# Midio.net
KiCad netlist of a schematic drawn in EAGLE
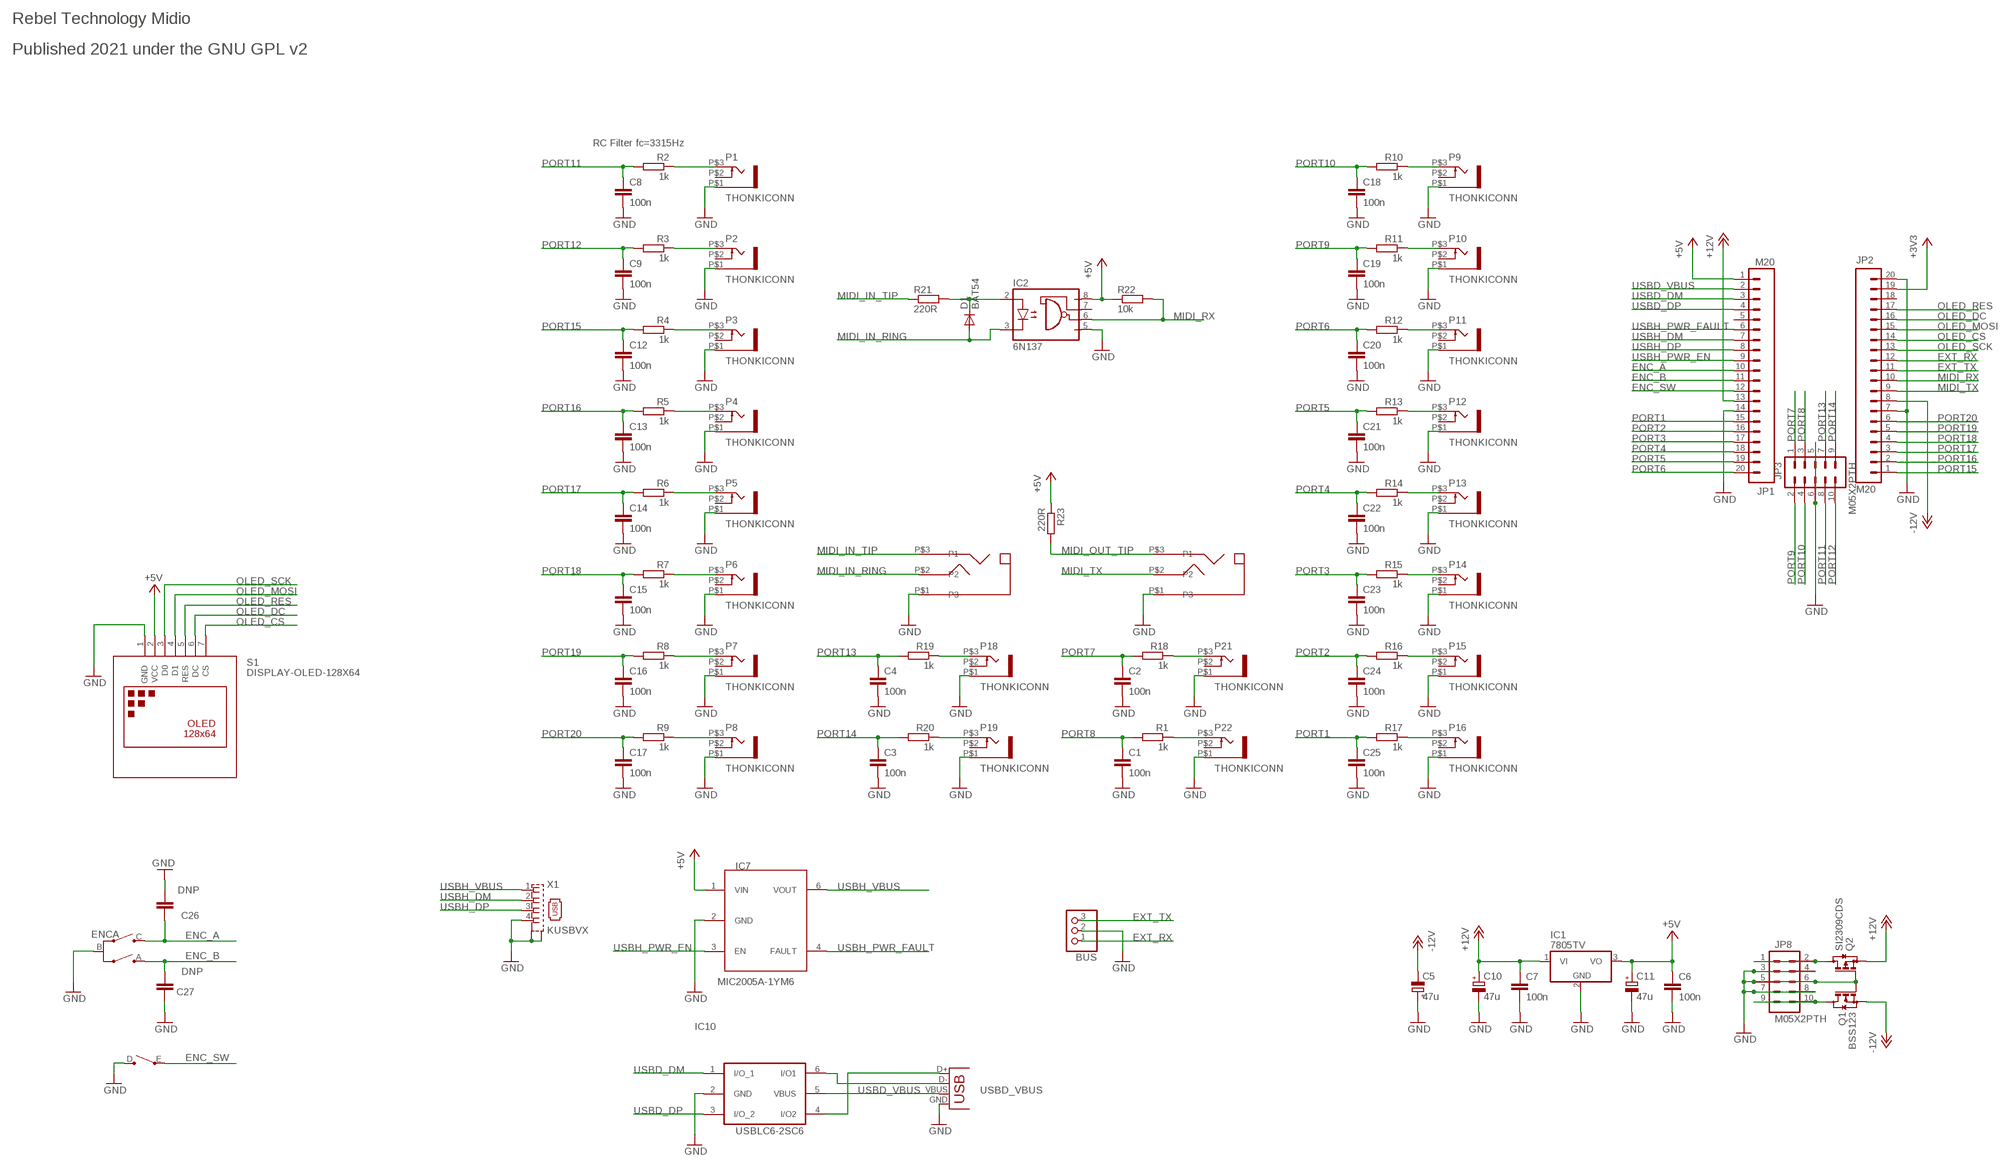
[diagram p0: schematic, sheet 1]

(export (version "E")
  (design (tool "Eeschema 10.0.6"))
  (components
    (comp (ref "BUS")
      (value "CON-JST-1X03PH-TH")
      (footprint "eagle-import:JST-B3B-PH-KL")
      (libsource (lib "eagle-import") (part "CON-JST-1X03PH-TH"))
    )
    (comp (ref "C1")
      (value "100n")
      (footprint "eagle-import:C0603")
      (libsource (lib "eagle-import") (part "C-EUC0603"))
    )
    (comp (ref "C2")
      (value "100n")
      (footprint "eagle-import:C0603")
      (libsource (lib "eagle-import") (part "C-EUC0603"))
    )
    (comp (ref "C3")
      (value "100n")
      (footprint "eagle-import:C0603")
      (libsource (lib "eagle-import") (part "C-EUC0603"))
    )
    (comp (ref "C4")
      (value "100n")
      (footprint "eagle-import:C0603")
      (libsource (lib "eagle-import") (part "C-EUC0603"))
    )
    (comp (ref "C5")
      (value "47u")
      (footprint "eagle-import:UD-4X5,8_NICHICON")
      (libsource (lib "eagle-import") (part "CPOL-EUUD-4X5,8"))
    )
    (comp (ref "C6")
      (value "100n")
      (footprint "eagle-import:C0603")
      (libsource (lib "eagle-import") (part "C-EUC0603"))
    )
    (comp (ref "C7")
      (value "100n")
      (footprint "eagle-import:C0603")
      (libsource (lib "eagle-import") (part "C-EUC0603"))
    )
    (comp (ref "C8")
      (value "100n")
      (footprint "eagle-import:C0603")
      (libsource (lib "eagle-import") (part "C-EUC0603"))
    )
    (comp (ref "C9")
      (value "100n")
      (footprint "eagle-import:C0603")
      (libsource (lib "eagle-import") (part "C-EUC0603"))
    )
    (comp (ref "C10")
      (value "47u")
      (footprint "eagle-import:UD-4X5,8_NICHICON")
      (libsource (lib "eagle-import") (part "CPOL-EUUD-4X5,8"))
    )
    (comp (ref "C11")
      (value "47u")
      (footprint "eagle-import:UD-4X5,8_NICHICON")
      (libsource (lib "eagle-import") (part "rcl_CPOL-EUUD-4X5,8"))
    )
    (comp (ref "C12")
      (value "100n")
      (footprint "eagle-import:C0603")
      (libsource (lib "eagle-import") (part "C-EUC0603"))
    )
    (comp (ref "C13")
      (value "100n")
      (footprint "eagle-import:C0603")
      (libsource (lib "eagle-import") (part "C-EUC0603"))
    )
    (comp (ref "C14")
      (value "100n")
      (footprint "eagle-import:C0603")
      (libsource (lib "eagle-import") (part "C-EUC0603"))
    )
    (comp (ref "C15")
      (value "100n")
      (footprint "eagle-import:C0603")
      (libsource (lib "eagle-import") (part "C-EUC0603"))
    )
    (comp (ref "C16")
      (value "100n")
      (footprint "eagle-import:C0603")
      (libsource (lib "eagle-import") (part "C-EUC0603"))
    )
    (comp (ref "C17")
      (value "100n")
      (footprint "eagle-import:C0603")
      (libsource (lib "eagle-import") (part "C-EUC0603"))
    )
    (comp (ref "C18")
      (value "100n")
      (footprint "eagle-import:C0603")
      (libsource (lib "eagle-import") (part "C-EUC0603"))
    )
    (comp (ref "C19")
      (value "100n")
      (footprint "eagle-import:C0603")
      (libsource (lib "eagle-import") (part "C-EUC0603"))
    )
    (comp (ref "C20")
      (value "100n")
      (footprint "eagle-import:C0603")
      (libsource (lib "eagle-import") (part "C-EUC0603"))
    )
    (comp (ref "C21")
      (value "100n")
      (footprint "eagle-import:C0603")
      (libsource (lib "eagle-import") (part "C-EUC0603"))
    )
    (comp (ref "C22")
      (value "100n")
      (footprint "eagle-import:C0603")
      (libsource (lib "eagle-import") (part "C-EUC0603"))
    )
    (comp (ref "C23")
      (value "100n")
      (footprint "eagle-import:C0603")
      (libsource (lib "eagle-import") (part "C-EUC0603"))
    )
    (comp (ref "C24")
      (value "100n")
      (footprint "eagle-import:C0603")
      (libsource (lib "eagle-import") (part "C-EUC0603"))
    )
    (comp (ref "C25")
      (value "100n")
      (footprint "eagle-import:C0603")
      (libsource (lib "eagle-import") (part "C-EUC0603"))
    )
    (comp (ref "C26")
      (value "DNP")
      (footprint "eagle-import:C0603")
      (libsource (lib "eagle-import") (part "rcl_C-EUC0603"))
    )
    (comp (ref "C27")
      (value "DNP")
      (footprint "eagle-import:C0603")
      (libsource (lib "eagle-import") (part "rcl_C-EUC0603"))
    )
    (comp (ref "D1")
      (value "BAT54")
      (footprint "eagle-import:SOT23-R")
      (libsource (lib "eagle-import") (part "DIODESOT23_REFLOW"))
    )
    (comp (ref "ENC")
      (value "CI-11")
      (footprint "eagle-import:CI-11")
      (libsource (lib "eagle-import") (part "CI-11"))
    )
    (comp (ref "IC1")
      (value "7805TV")
      (footprint "eagle-import:TO220V")
      (libsource (lib "eagle-import") (part "78TV05"))
    )
    (comp (ref "IC2")
      (value "6N137")
      (footprint "eagle-import:DIL08")
      (libsource (lib "eagle-import") (part "6N137"))
    )
    (comp (ref "IC7")
      (value "MIC2005A-1YM6")
      (footprint "eagle-import:SOT23-6")
      (libsource (lib "eagle-import") (part "MIC2005"))
    )
    (comp (ref "IC10")
      (value "USBLC6-2SC6")
      (footprint "eagle-import:SOT-23-6L")
      (libsource (lib "eagle-import") (part "USBLC6-2SC6"))
    )
    (comp (ref "J1")
      (value "THONKICONN_STEREO")
      (footprint "eagle-import:THONKICONN_STEREO")
      (libsource (lib "eagle-import") (part "THONKICONN_STEREO"))
    )
    (comp (ref "J2")
      (value "THONKICONN_STEREO")
      (footprint "eagle-import:THONKICONN_STEREO")
      (libsource (lib "eagle-import") (part "THONKICONN_STEREO"))
    )
    (comp (ref "JP1")
      (value "M20")
      (footprint "eagle-import:1X20")
      (libsource (lib "eagle-import") (part "M20"))
    )
    (comp (ref "JP2")
      (value "M20")
      (footprint "eagle-import:1X20")
      (libsource (lib "eagle-import") (part "M20"))
    )
    (comp (ref "JP3")
      (value "M05X2PTH")
      (footprint "eagle-import:AVR_ICSP")
      (libsource (lib "eagle-import") (part "M05X2PTH"))
    )
    (comp (ref "JP8")
      (value "M05X2PTH")
      (footprint "eagle-import:AVR_ICSP")
      (libsource (lib "eagle-import") (part "M05X2PTH"))
    )
    (comp (ref "P1")
      (value "THONKICONN")
      (footprint "eagle-import:THONKICONN")
      (libsource (lib "eagle-import") (part "THONKICONN"))
    )
    (comp (ref "P2")
      (value "THONKICONN")
      (footprint "eagle-import:THONKICONN")
      (libsource (lib "eagle-import") (part "THONKICONN"))
    )
    (comp (ref "P3")
      (value "THONKICONN")
      (footprint "eagle-import:THONKICONN")
      (libsource (lib "eagle-import") (part "THONKICONN"))
    )
    (comp (ref "P4")
      (value "THONKICONN")
      (footprint "eagle-import:THONKICONN")
      (libsource (lib "eagle-import") (part "THONKICONN"))
    )
    (comp (ref "P5")
      (value "THONKICONN")
      (footprint "eagle-import:THONKICONN")
      (libsource (lib "eagle-import") (part "THONKICONN"))
    )
    (comp (ref "P6")
      (value "THONKICONN")
      (footprint "eagle-import:THONKICONN")
      (libsource (lib "eagle-import") (part "THONKICONN"))
    )
    (comp (ref "P7")
      (value "THONKICONN")
      (footprint "eagle-import:THONKICONN")
      (libsource (lib "eagle-import") (part "THONKICONN"))
    )
    (comp (ref "P8")
      (value "THONKICONN")
      (footprint "eagle-import:THONKICONN")
      (libsource (lib "eagle-import") (part "THONKICONN"))
    )
    (comp (ref "P9")
      (value "THONKICONN")
      (footprint "eagle-import:THONKICONN")
      (libsource (lib "eagle-import") (part "THONKICONN"))
    )
    (comp (ref "P10")
      (value "THONKICONN")
      (footprint "eagle-import:THONKICONN")
      (libsource (lib "eagle-import") (part "THONKICONN"))
    )
    (comp (ref "P11")
      (value "THONKICONN")
      (footprint "eagle-import:THONKICONN")
      (libsource (lib "eagle-import") (part "THONKICONN"))
    )
    (comp (ref "P12")
      (value "THONKICONN")
      (footprint "eagle-import:THONKICONN")
      (libsource (lib "eagle-import") (part "THONKICONN"))
    )
    (comp (ref "P13")
      (value "THONKICONN")
      (footprint "eagle-import:THONKICONN")
      (libsource (lib "eagle-import") (part "THONKICONN"))
    )
    (comp (ref "P14")
      (value "THONKICONN")
      (footprint "eagle-import:THONKICONN")
      (libsource (lib "eagle-import") (part "THONKICONN"))
    )
    (comp (ref "P15")
      (value "THONKICONN")
      (footprint "eagle-import:THONKICONN")
      (libsource (lib "eagle-import") (part "THONKICONN"))
    )
    (comp (ref "P16")
      (value "THONKICONN")
      (footprint "eagle-import:THONKICONN")
      (libsource (lib "eagle-import") (part "THONKICONN"))
    )
    (comp (ref "P18")
      (value "THONKICONN")
      (footprint "eagle-import:THONKICONN")
      (libsource (lib "eagle-import") (part "THONKICONN"))
    )
    (comp (ref "P19")
      (value "THONKICONN")
      (footprint "eagle-import:THONKICONN")
      (libsource (lib "eagle-import") (part "THONKICONN"))
    )
    (comp (ref "P21")
      (value "THONKICONN")
      (footprint "eagle-import:THONKICONN")
      (libsource (lib "eagle-import") (part "THONKICONN"))
    )
    (comp (ref "P22")
      (value "THONKICONN")
      (footprint "eagle-import:THONKICONN")
      (libsource (lib "eagle-import") (part "THONKICONN"))
    )
    (comp (ref "Q1")
      (value "BSS123")
      (footprint "eagle-import:SOT23")
      (libsource (lib "eagle-import") (part "BSS123"))
    )
    (comp (ref "Q2")
      (value "SI2309CDS")
      (footprint "eagle-import:SOT23")
      (libsource (lib "eagle-import") (part "BSS84"))
    )
    (comp (ref "R1")
      (value "1k")
      (footprint "eagle-import:0603")
      (libsource (lib "eagle-import") (part "R-EU_0603"))
    )
    (comp (ref "R2")
      (value "1k")
      (footprint "eagle-import:0603")
      (libsource (lib "eagle-import") (part "R-EU_0603"))
    )
    (comp (ref "R3")
      (value "1k")
      (footprint "eagle-import:0603")
      (libsource (lib "eagle-import") (part "R-EU_0603"))
    )
    (comp (ref "R4")
      (value "1k")
      (footprint "eagle-import:0603")
      (libsource (lib "eagle-import") (part "R-EU_0603"))
    )
    (comp (ref "R5")
      (value "1k")
      (footprint "eagle-import:0603")
      (libsource (lib "eagle-import") (part "R-EU_0603"))
    )
    (comp (ref "R6")
      (value "1k")
      (footprint "eagle-import:0603")
      (libsource (lib "eagle-import") (part "R-EU_0603"))
    )
    (comp (ref "R7")
      (value "1k")
      (footprint "eagle-import:0603")
      (libsource (lib "eagle-import") (part "R-EU_0603"))
    )
    (comp (ref "R8")
      (value "1k")
      (footprint "eagle-import:0603")
      (libsource (lib "eagle-import") (part "R-EU_0603"))
    )
    (comp (ref "R9")
      (value "1k")
      (footprint "eagle-import:0603")
      (libsource (lib "eagle-import") (part "R-EU_0603"))
    )
    (comp (ref "R10")
      (value "1k")
      (footprint "eagle-import:0603")
      (libsource (lib "eagle-import") (part "R-EU_0603"))
    )
    (comp (ref "R11")
      (value "1k")
      (footprint "eagle-import:0603")
      (libsource (lib "eagle-import") (part "R-EU_0603"))
    )
    (comp (ref "R12")
      (value "1k")
      (footprint "eagle-import:0603")
      (libsource (lib "eagle-import") (part "R-EU_0603"))
    )
    (comp (ref "R13")
      (value "1k")
      (footprint "eagle-import:0603")
      (libsource (lib "eagle-import") (part "R-EU_0603"))
    )
    (comp (ref "R14")
      (value "1k")
      (footprint "eagle-import:0603")
      (libsource (lib "eagle-import") (part "R-EU_0603"))
    )
    (comp (ref "R15")
      (value "1k")
      (footprint "eagle-import:0603")
      (libsource (lib "eagle-import") (part "R-EU_0603"))
    )
    (comp (ref "R16")
      (value "1k")
      (footprint "eagle-import:0603")
      (libsource (lib "eagle-import") (part "R-EU_0603"))
    )
    (comp (ref "R17")
      (value "1k")
      (footprint "eagle-import:0603")
      (libsource (lib "eagle-import") (part "R-EU_0603"))
    )
    (comp (ref "R18")
      (value "1k")
      (footprint "eagle-import:0603")
      (libsource (lib "eagle-import") (part "R-EU_0603"))
    )
    (comp (ref "R19")
      (value "1k")
      (footprint "eagle-import:0603")
      (libsource (lib "eagle-import") (part "R-EU_0603"))
    )
    (comp (ref "R20")
      (value "1k")
      (footprint "eagle-import:0603")
      (libsource (lib "eagle-import") (part "R-EU_0603"))
    )
    (comp (ref "R21")
      (value "220R")
      (footprint "eagle-import:0603")
      (libsource (lib "eagle-import") (part "Rebel_15457297_R-EU_0603"))
    )
    (comp (ref "R22")
      (value "10k")
      (footprint "eagle-import:0603")
      (libsource (lib "eagle-import") (part "Rebel_15457297_R-EU_0603"))
    )
    (comp (ref "R23")
      (value "220R")
      (footprint "eagle-import:0603")
      (libsource (lib "eagle-import") (part "Rebel_15457297_R-EU_0603"))
    )
    (comp (ref "S1")
      (value "DISPLAY-OLED-128X64")
      (footprint "eagle-import:DISPLAY-OLED-128X64")
      (libsource (lib "eagle-import") (part "DISPLAY-OLED-128X64"))
    )
    (comp (ref "X1")
      (value "KUSBVX")
      (footprint "eagle-import:KUSBVX")
      (libsource (lib "eagle-import") (part "KUSBVX"))
    )
    (comp (ref "X2")
      (value "USBPTH-VERTICAL")
      (footprint "eagle-import:USB-B-PTH-VERTICAL")
      (libsource (lib "eagle-import") (part "USBPTH-VERTICAL"))
    )
  )
  (nets
    (net (code "1") (name "+3V3") (class "Default")
      (node (ref "JP2") (pin "19") (pinfunction "19_19") (pintype "passive"))
    )
    (net (code "2") (name "+5V") (class "Default")
      (node (ref "C11") (pin "+") (pinfunction "+_+") (pintype "passive"))
      (node (ref "C6") (pin "1") (pinfunction "1_1") (pintype "passive"))
      (node (ref "IC1") (pin "3") (pinfunction "VO_3") (pintype "passive"))
      (node (ref "IC2") (pin "8") (pinfunction "VCC_8") (pintype "passive"))
      (node (ref "IC7") (pin "1") (pinfunction "VIN_1") (pintype "power_in"))
      (node (ref "JP1") (pin "1") (pinfunction "1_1") (pintype "passive"))
      (node (ref "R22") (pin "1") (pinfunction "1_1") (pintype "passive"))
      (node (ref "R23") (pin "1") (pinfunction "1_1") (pintype "passive"))
      (node (ref "S1") (pin "2") (pinfunction "VCC_2") (pintype "power_in"))
    )
    (net (code "3") (name "+12V") (class "Default")
      (node (ref "C10") (pin "+") (pinfunction "+_+") (pintype "passive"))
      (node (ref "C7") (pin "1") (pinfunction "1_1") (pintype "passive"))
      (node (ref "IC1") (pin "1") (pinfunction "VI_1") (pintype "input"))
      (node (ref "JP1") (pin "13") (pinfunction "13_13") (pintype "passive"))
      (node (ref "Q2") (pin "2") (pinfunction "S_2") (pintype "passive"))
    )
    (net (code "4") (name "-12V") (class "Default")
      (node (ref "C5") (pin "-") (pinfunction "-_-") (pintype "passive"))
      (node (ref "JP2") (pin "8") (pinfunction "8_8") (pintype "passive"))
      (node (ref "Q1") (pin "2") (pinfunction "S_2") (pintype "passive"))
    )
    (net (code "5") (name "/ENC_A") (class "Default")
      (node (ref "C26") (pin "1") (pinfunction "1_1") (pintype "passive"))
      (node (ref "ENC") (pin "C") (pinfunction "B_C") (pintype "passive"))
      (node (ref "JP1") (pin "10") (pinfunction "10_10") (pintype "passive"))
    )
    (net (code "6") (name "/ENC_B") (class "Default")
      (node (ref "C27") (pin "1") (pinfunction "1_1") (pintype "passive"))
      (node (ref "ENC") (pin "A") (pinfunction "A_A") (pintype "passive"))
      (node (ref "JP1") (pin "11") (pinfunction "11_11") (pintype "passive"))
    )
    (net (code "7") (name "/ENC_SW") (class "Default")
      (node (ref "ENC") (pin "E") (pinfunction "E_E") (pintype "passive"))
      (node (ref "JP1") (pin "12") (pinfunction "12_12") (pintype "passive"))
    )
    (net (code "8") (name "/EXT_RX") (class "Default")
      (node (ref "BUS") (pin "1") (pinfunction "1_1") (pintype "passive"))
      (node (ref "JP2") (pin "12") (pinfunction "12_12") (pintype "passive"))
    )
    (net (code "9") (name "/EXT_TX") (class "Default")
      (node (ref "BUS") (pin "3") (pinfunction "3_3") (pintype "passive"))
      (node (ref "JP2") (pin "11") (pinfunction "11_11") (pintype "passive"))
    )
    (net (code "10") (name "/MIDI_IN_RING") (class "Default")
      (node (ref "D1") (pin "1") (pinfunction "A_1") (pintype "passive"))
      (node (ref "IC2") (pin "3") (pinfunction "C_3") (pintype "passive"))
      (node (ref "J1") (pin "P$2") (pinfunction "P2_P$2") (pintype "bidirectional"))
    )
    (net (code "11") (name "/MIDI_IN_TIP") (class "Default")
      (node (ref "J1") (pin "P$3") (pinfunction "P1_P$3") (pintype "bidirectional"))
      (node (ref "R21") (pin "1") (pinfunction "1_1") (pintype "passive"))
    )
    (net (code "12") (name "/MIDI_OUT_TIP") (class "Default")
      (node (ref "J2") (pin "P$3") (pinfunction "P1_P$3") (pintype "bidirectional"))
      (node (ref "R23") (pin "2") (pinfunction "2_2") (pintype "passive"))
    )
    (net (code "13") (name "/MIDI_RX") (class "Default")
      (node (ref "IC2") (pin "6") (pinfunction "VO_6") (pintype "passive"))
      (node (ref "JP2") (pin "10") (pinfunction "10_10") (pintype "passive"))
      (node (ref "R22") (pin "2") (pinfunction "2_2") (pintype "passive"))
    )
    (net (code "14") (name "/MIDI_TX") (class "Default")
      (node (ref "J2") (pin "P$2") (pinfunction "P2_P$2") (pintype "bidirectional"))
      (node (ref "JP2") (pin "9") (pinfunction "9_9") (pintype "passive"))
    )
    (net (code "15") (name "/OLED_CS") (class "Default")
      (node (ref "JP2") (pin "14") (pinfunction "14_14") (pintype "passive"))
      (node (ref "S1") (pin "7") (pinfunction "CS_7") (pintype "bidirectional"))
    )
    (net (code "16") (name "/OLED_DC") (class "Default")
      (node (ref "JP2") (pin "16") (pinfunction "16_16") (pintype "passive"))
      (node (ref "S1") (pin "6") (pinfunction "DC_6") (pintype "bidirectional"))
    )
    (net (code "17") (name "/OLED_MOSI") (class "Default")
      (node (ref "JP2") (pin "15") (pinfunction "15_15") (pintype "passive"))
      (node (ref "S1") (pin "4") (pinfunction "D1_4") (pintype "bidirectional"))
    )
    (net (code "18") (name "/OLED_RES") (class "Default")
      (node (ref "JP2") (pin "17") (pinfunction "17_17") (pintype "passive"))
      (node (ref "S1") (pin "5") (pinfunction "RES_5") (pintype "bidirectional"))
    )
    (net (code "19") (name "/OLED_SCK") (class "Default")
      (node (ref "JP2") (pin "13") (pinfunction "13_13") (pintype "passive"))
      (node (ref "S1") (pin "3") (pinfunction "D0_3") (pintype "bidirectional"))
    )
    (net (code "20") (name "/PORT1") (class "Default")
      (node (ref "C25") (pin "1") (pinfunction "1_1") (pintype "passive"))
      (node (ref "JP1") (pin "15") (pinfunction "15_15") (pintype "passive"))
      (node (ref "R17") (pin "2") (pinfunction "2_2") (pintype "passive"))
    )
    (net (code "21") (name "/PORT2") (class "Default")
      (node (ref "C24") (pin "1") (pinfunction "1_1") (pintype "passive"))
      (node (ref "JP1") (pin "16") (pinfunction "16_16") (pintype "passive"))
      (node (ref "R16") (pin "2") (pinfunction "2_2") (pintype "passive"))
    )
    (net (code "22") (name "/PORT3") (class "Default")
      (node (ref "C23") (pin "1") (pinfunction "1_1") (pintype "passive"))
      (node (ref "JP1") (pin "17") (pinfunction "17_17") (pintype "passive"))
      (node (ref "R15") (pin "2") (pinfunction "2_2") (pintype "passive"))
    )
    (net (code "23") (name "/PORT4") (class "Default")
      (node (ref "C22") (pin "1") (pinfunction "1_1") (pintype "passive"))
      (node (ref "JP1") (pin "18") (pinfunction "18_18") (pintype "passive"))
      (node (ref "R14") (pin "2") (pinfunction "2_2") (pintype "passive"))
    )
    (net (code "24") (name "/PORT5") (class "Default")
      (node (ref "C21") (pin "1") (pinfunction "1_1") (pintype "passive"))
      (node (ref "JP1") (pin "19") (pinfunction "19_19") (pintype "passive"))
      (node (ref "R13") (pin "2") (pinfunction "2_2") (pintype "passive"))
    )
    (net (code "25") (name "/PORT6") (class "Default")
      (node (ref "C20") (pin "1") (pinfunction "1_1") (pintype "passive"))
      (node (ref "JP1") (pin "20") (pinfunction "20_20") (pintype "passive"))
      (node (ref "R12") (pin "2") (pinfunction "2_2") (pintype "passive"))
    )
    (net (code "26") (name "/PORT7") (class "Default")
      (node (ref "C2") (pin "1") (pinfunction "1_1") (pintype "passive"))
      (node (ref "JP3") (pin "1") (pinfunction "1_1") (pintype "passive"))
      (node (ref "R18") (pin "2") (pinfunction "2_2") (pintype "passive"))
    )
    (net (code "27") (name "/PORT8") (class "Default")
      (node (ref "C1") (pin "1") (pinfunction "1_1") (pintype "passive"))
      (node (ref "JP3") (pin "3") (pinfunction "3_3") (pintype "passive"))
      (node (ref "R1") (pin "2") (pinfunction "2_2") (pintype "passive"))
    )
    (net (code "28") (name "/PORT9") (class "Default")
      (node (ref "C19") (pin "1") (pinfunction "1_1") (pintype "passive"))
      (node (ref "JP3") (pin "2") (pinfunction "2_2") (pintype "passive"))
      (node (ref "R11") (pin "2") (pinfunction "2_2") (pintype "passive"))
    )
    (net (code "29") (name "/PORT10") (class "Default")
      (node (ref "C18") (pin "1") (pinfunction "1_1") (pintype "passive"))
      (node (ref "JP3") (pin "4") (pinfunction "4_4") (pintype "passive"))
      (node (ref "R10") (pin "2") (pinfunction "2_2") (pintype "passive"))
    )
    (net (code "30") (name "/PORT11") (class "Default")
      (node (ref "C8") (pin "1") (pinfunction "1_1") (pintype "passive"))
      (node (ref "JP3") (pin "8") (pinfunction "8_8") (pintype "passive"))
      (node (ref "R2") (pin "2") (pinfunction "2_2") (pintype "passive"))
    )
    (net (code "31") (name "/PORT12") (class "Default")
      (node (ref "C9") (pin "1") (pinfunction "1_1") (pintype "passive"))
      (node (ref "JP3") (pin "10") (pinfunction "10_10") (pintype "passive"))
      (node (ref "R3") (pin "2") (pinfunction "2_2") (pintype "passive"))
    )
    (net (code "32") (name "/PORT13") (class "Default")
      (node (ref "C4") (pin "1") (pinfunction "1_1") (pintype "passive"))
      (node (ref "JP3") (pin "7") (pinfunction "7_7") (pintype "passive"))
      (node (ref "R19") (pin "2") (pinfunction "2_2") (pintype "passive"))
    )
    (net (code "33") (name "/PORT14") (class "Default")
      (node (ref "C3") (pin "1") (pinfunction "1_1") (pintype "passive"))
      (node (ref "JP3") (pin "9") (pinfunction "9_9") (pintype "passive"))
      (node (ref "R20") (pin "2") (pinfunction "2_2") (pintype "passive"))
    )
    (net (code "34") (name "/PORT15") (class "Default")
      (node (ref "C12") (pin "1") (pinfunction "1_1") (pintype "passive"))
      (node (ref "JP2") (pin "1") (pinfunction "1_1") (pintype "passive"))
      (node (ref "R4") (pin "2") (pinfunction "2_2") (pintype "passive"))
    )
    (net (code "35") (name "/PORT16") (class "Default")
      (node (ref "C13") (pin "1") (pinfunction "1_1") (pintype "passive"))
      (node (ref "JP2") (pin "2") (pinfunction "2_2") (pintype "passive"))
      (node (ref "R5") (pin "2") (pinfunction "2_2") (pintype "passive"))
    )
    (net (code "36") (name "/PORT17") (class "Default")
      (node (ref "C14") (pin "1") (pinfunction "1_1") (pintype "passive"))
      (node (ref "JP2") (pin "3") (pinfunction "3_3") (pintype "passive"))
      (node (ref "R6") (pin "2") (pinfunction "2_2") (pintype "passive"))
    )
    (net (code "37") (name "/PORT18") (class "Default")
      (node (ref "C15") (pin "1") (pinfunction "1_1") (pintype "passive"))
      (node (ref "JP2") (pin "4") (pinfunction "4_4") (pintype "passive"))
      (node (ref "R7") (pin "2") (pinfunction "2_2") (pintype "passive"))
    )
    (net (code "38") (name "/PORT19") (class "Default")
      (node (ref "C16") (pin "1") (pinfunction "1_1") (pintype "passive"))
      (node (ref "JP2") (pin "5") (pinfunction "5_5") (pintype "passive"))
      (node (ref "R8") (pin "2") (pinfunction "2_2") (pintype "passive"))
    )
    (net (code "39") (name "/PORT20") (class "Default")
      (node (ref "C17") (pin "1") (pinfunction "1_1") (pintype "passive"))
      (node (ref "JP2") (pin "6") (pinfunction "6_6") (pintype "passive"))
      (node (ref "R9") (pin "2") (pinfunction "2_2") (pintype "passive"))
    )
    (net (code "40") (name "/USBD_DM") (class "Default")
      (node (ref "IC10") (pin "1") (pinfunction "I/O_1_1") (pintype "bidirectional"))
      (node (ref "JP1") (pin "3") (pinfunction "3_3") (pintype "passive"))
    )
    (net (code "41") (name "/USBD_DP") (class "Default")
      (node (ref "IC10") (pin "3") (pinfunction "I/O_2_3") (pintype "bidirectional"))
      (node (ref "JP1") (pin "4") (pinfunction "4_4") (pintype "passive"))
    )
    (net (code "42") (name "/USBD_VBUS") (class "Default")
      (node (ref "IC10") (pin "5") (pinfunction "VBUS_5") (pintype "bidirectional"))
      (node (ref "JP1") (pin "2") (pinfunction "2_2") (pintype "passive"))
      (node (ref "X2") (pin "VBUS") (pinfunction "VBUS_VBUS") (pintype "bidirectional"))
    )
    (net (code "43") (name "/USBH_DM") (class "Default")
      (node (ref "JP1") (pin "7") (pinfunction "7_7") (pintype "passive"))
      (node (ref "X1") (pin "2") (pinfunction "2_2") (pintype "passive"))
    )
    (net (code "44") (name "/USBH_DP") (class "Default")
      (node (ref "JP1") (pin "8") (pinfunction "8_8") (pintype "passive"))
      (node (ref "X1") (pin "3") (pinfunction "3_3") (pintype "passive"))
    )
    (net (code "45") (name "/USBH_PWR_EN") (class "Default")
      (node (ref "IC7") (pin "3") (pinfunction "EN_3") (pintype "input"))
      (node (ref "JP1") (pin "9") (pinfunction "9_9") (pintype "passive"))
    )
    (net (code "46") (name "/USBH_PWR_FAULT") (class "Default")
      (node (ref "IC7") (pin "4") (pinfunction "FAULT_4") (pintype "output"))
      (node (ref "JP1") (pin "6") (pinfunction "6_6") (pintype "passive"))
    )
    (net (code "47") (name "/USBH_VBUS") (class "Default")
      (node (ref "IC7") (pin "6") (pinfunction "VOUT_6") (pintype "output"))
      (node (ref "X1") (pin "1") (pinfunction "1_1") (pintype "passive"))
    )
    (net (code "48") (name "GND") (class "Default")
      (node (ref "BUS") (pin "2") (pinfunction "2_2") (pintype "passive"))
      (node (ref "C1") (pin "2") (pinfunction "2_2") (pintype "passive"))
      (node (ref "C10") (pin "-") (pinfunction "-_-") (pintype "passive"))
      (node (ref "C11") (pin "-") (pinfunction "-_-") (pintype "passive"))
      (node (ref "C12") (pin "2") (pinfunction "2_2") (pintype "passive"))
      (node (ref "C13") (pin "2") (pinfunction "2_2") (pintype "passive"))
      (node (ref "C14") (pin "2") (pinfunction "2_2") (pintype "passive"))
      (node (ref "C15") (pin "2") (pinfunction "2_2") (pintype "passive"))
      (node (ref "C16") (pin "2") (pinfunction "2_2") (pintype "passive"))
      (node (ref "C17") (pin "2") (pinfunction "2_2") (pintype "passive"))
      (node (ref "C18") (pin "2") (pinfunction "2_2") (pintype "passive"))
      (node (ref "C19") (pin "2") (pinfunction "2_2") (pintype "passive"))
      (node (ref "C2") (pin "2") (pinfunction "2_2") (pintype "passive"))
      (node (ref "C20") (pin "2") (pinfunction "2_2") (pintype "passive"))
      (node (ref "C21") (pin "2") (pinfunction "2_2") (pintype "passive"))
      (node (ref "C22") (pin "2") (pinfunction "2_2") (pintype "passive"))
      (node (ref "C23") (pin "2") (pinfunction "2_2") (pintype "passive"))
      (node (ref "C24") (pin "2") (pinfunction "2_2") (pintype "passive"))
      (node (ref "C25") (pin "2") (pinfunction "2_2") (pintype "passive"))
      (node (ref "C26") (pin "2") (pinfunction "2_2") (pintype "passive"))
      (node (ref "C27") (pin "2") (pinfunction "2_2") (pintype "passive"))
      (node (ref "C3") (pin "2") (pinfunction "2_2") (pintype "passive"))
      (node (ref "C4") (pin "2") (pinfunction "2_2") (pintype "passive"))
      (node (ref "C5") (pin "+") (pinfunction "+_+") (pintype "passive"))
      (node (ref "C6") (pin "2") (pinfunction "2_2") (pintype "passive"))
      (node (ref "C7") (pin "2") (pinfunction "2_2") (pintype "passive"))
      (node (ref "C8") (pin "2") (pinfunction "2_2") (pintype "passive"))
      (node (ref "C9") (pin "2") (pinfunction "2_2") (pintype "passive"))
      (node (ref "ENC") (pin "B") (pinfunction "C_B") (pintype "passive"))
      (node (ref "ENC") (pin "D") (pinfunction "D_D") (pintype "passive"))
      (node (ref "IC1") (pin "2") (pinfunction "GND_2") (pintype "passive"))
      (node (ref "IC10") (pin "2") (pinfunction "GND_2") (pintype "bidirectional"))
      (node (ref "IC2") (pin "5") (pinfunction "GND_5") (pintype "passive"))
      (node (ref "IC7") (pin "2") (pinfunction "GND_2") (pintype "power_in"))
      (node (ref "J1") (pin "P$1") (pinfunction "P3_P$1") (pintype "bidirectional"))
      (node (ref "J2") (pin "P$1") (pinfunction "P3_P$1") (pintype "bidirectional"))
      (node (ref "JP1") (pin "14") (pinfunction "14_14") (pintype "passive"))
      (node (ref "JP2") (pin "20") (pinfunction "20_20") (pintype "passive"))
      (node (ref "JP2") (pin "7") (pinfunction "7_7") (pintype "passive"))
      (node (ref "JP3") (pin "5") (pinfunction "5_5") (pintype "passive"))
      (node (ref "JP3") (pin "6") (pinfunction "6_6") (pintype "passive"))
      (node (ref "JP8") (pin "3") (pinfunction "3_3") (pintype "passive"))
      (node (ref "JP8") (pin "4") (pinfunction "4_4") (pintype "passive"))
      (node (ref "JP8") (pin "5") (pinfunction "5_5") (pintype "passive"))
      (node (ref "JP8") (pin "6") (pinfunction "6_6") (pintype "passive"))
      (node (ref "JP8") (pin "7") (pinfunction "7_7") (pintype "passive"))
      (node (ref "JP8") (pin "8") (pinfunction "8_8") (pintype "passive"))
      (node (ref "P1") (pin "P$1") (pinfunction "5_P$1") (pintype "passive"))
      (node (ref "P10") (pin "P$1") (pinfunction "5_P$1") (pintype "passive"))
      (node (ref "P11") (pin "P$1") (pinfunction "5_P$1") (pintype "passive"))
      (node (ref "P12") (pin "P$1") (pinfunction "5_P$1") (pintype "passive"))
      (node (ref "P13") (pin "P$1") (pinfunction "5_P$1") (pintype "passive"))
      (node (ref "P14") (pin "P$1") (pinfunction "5_P$1") (pintype "passive"))
      (node (ref "P15") (pin "P$1") (pinfunction "5_P$1") (pintype "passive"))
      (node (ref "P16") (pin "P$1") (pinfunction "5_P$1") (pintype "passive"))
      (node (ref "P18") (pin "P$1") (pinfunction "5_P$1") (pintype "passive"))
      (node (ref "P19") (pin "P$1") (pinfunction "5_P$1") (pintype "passive"))
      (node (ref "P2") (pin "P$1") (pinfunction "5_P$1") (pintype "passive"))
      (node (ref "P21") (pin "P$1") (pinfunction "5_P$1") (pintype "passive"))
      (node (ref "P22") (pin "P$1") (pinfunction "5_P$1") (pintype "passive"))
      (node (ref "P3") (pin "P$1") (pinfunction "5_P$1") (pintype "passive"))
      (node (ref "P4") (pin "P$1") (pinfunction "5_P$1") (pintype "passive"))
      (node (ref "P5") (pin "P$1") (pinfunction "5_P$1") (pintype "passive"))
      (node (ref "P6") (pin "P$1") (pinfunction "5_P$1") (pintype "passive"))
      (node (ref "P7") (pin "P$1") (pinfunction "5_P$1") (pintype "passive"))
      (node (ref "P8") (pin "P$1") (pinfunction "5_P$1") (pintype "passive"))
      (node (ref "P9") (pin "P$1") (pinfunction "5_P$1") (pintype "passive"))
      (node (ref "Q1") (pin "1") (pinfunction "G_1") (pintype "passive"))
      (node (ref "Q2") (pin "1") (pinfunction "G_1") (pintype "passive"))
      (node (ref "S1") (pin "1") (pinfunction "GND_1") (pintype "power_in"))
      (node (ref "X1") (pin "4") (pinfunction "4_4") (pintype "passive"))
      (node (ref "X1") (pin "M1") (pinfunction "S1_M1") (pintype "passive"))
      (node (ref "X1") (pin "M2") (pinfunction "S2_M2") (pintype "passive"))
      (node (ref "X2") (pin "GND") (pinfunction "GND_GND") (pintype "bidirectional"))
    )
    (net (code "49") (name "Net-(D1-C)") (class "Default")
      (node (ref "D1") (pin "3") (pinfunction "C_3") (pintype "passive"))
      (node (ref "IC2") (pin "2") (pinfunction "A_2") (pintype "passive"))
      (node (ref "R21") (pin "2") (pinfunction "2_2") (pintype "passive"))
    )
    (net (code "50") (name "Net-(IC10-I{slash}O1)") (class "Default")
      (node (ref "IC10") (pin "6") (pinfunction "I/O1_6") (pintype "bidirectional"))
      (node (ref "X2") (pin "D-") (pinfunction "D-_D-") (pintype "bidirectional"))
    )
    (net (code "51") (name "Net-(IC10-I{slash}O2)") (class "Default")
      (node (ref "IC10") (pin "4") (pinfunction "I/O2_4") (pintype "bidirectional"))
      (node (ref "X2") (pin "D+") (pinfunction "D+_D+") (pintype "bidirectional"))
    )
    (net (code "52") (name "Net-(P1-3)") (class "Default")
      (node (ref "P1") (pin "P$3") (pinfunction "3_P$3") (pintype "passive"))
      (node (ref "R2") (pin "1") (pinfunction "1_1") (pintype "passive"))
    )
    (net (code "53") (name "Net-(P2-3)") (class "Default")
      (node (ref "P2") (pin "P$3") (pinfunction "3_P$3") (pintype "passive"))
      (node (ref "R3") (pin "1") (pinfunction "1_1") (pintype "passive"))
    )
    (net (code "54") (name "Net-(P3-3)") (class "Default")
      (node (ref "P3") (pin "P$3") (pinfunction "3_P$3") (pintype "passive"))
      (node (ref "R4") (pin "1") (pinfunction "1_1") (pintype "passive"))
    )
    (net (code "55") (name "Net-(P4-3)") (class "Default")
      (node (ref "P4") (pin "P$3") (pinfunction "3_P$3") (pintype "passive"))
      (node (ref "R5") (pin "1") (pinfunction "1_1") (pintype "passive"))
    )
    (net (code "56") (name "Net-(P5-3)") (class "Default")
      (node (ref "P5") (pin "P$3") (pinfunction "3_P$3") (pintype "passive"))
      (node (ref "R6") (pin "1") (pinfunction "1_1") (pintype "passive"))
    )
    (net (code "57") (name "Net-(P6-3)") (class "Default")
      (node (ref "P6") (pin "P$3") (pinfunction "3_P$3") (pintype "passive"))
      (node (ref "R7") (pin "1") (pinfunction "1_1") (pintype "passive"))
    )
    (net (code "58") (name "Net-(P7-3)") (class "Default")
      (node (ref "P7") (pin "P$3") (pinfunction "3_P$3") (pintype "passive"))
      (node (ref "R8") (pin "1") (pinfunction "1_1") (pintype "passive"))
    )
    (net (code "59") (name "Net-(P8-3)") (class "Default")
      (node (ref "P8") (pin "P$3") (pinfunction "3_P$3") (pintype "passive"))
      (node (ref "R9") (pin "1") (pinfunction "1_1") (pintype "passive"))
    )
    (net (code "60") (name "Net-(P9-3)") (class "Default")
      (node (ref "P9") (pin "P$3") (pinfunction "3_P$3") (pintype "passive"))
      (node (ref "R10") (pin "1") (pinfunction "1_1") (pintype "passive"))
    )
    (net (code "61") (name "Net-(P10-3)") (class "Default")
      (node (ref "P10") (pin "P$3") (pinfunction "3_P$3") (pintype "passive"))
      (node (ref "R11") (pin "1") (pinfunction "1_1") (pintype "passive"))
    )
    (net (code "62") (name "Net-(P11-3)") (class "Default")
      (node (ref "P11") (pin "P$3") (pinfunction "3_P$3") (pintype "passive"))
      (node (ref "R12") (pin "1") (pinfunction "1_1") (pintype "passive"))
    )
    (net (code "63") (name "Net-(P12-3)") (class "Default")
      (node (ref "P12") (pin "P$3") (pinfunction "3_P$3") (pintype "passive"))
      (node (ref "R13") (pin "1") (pinfunction "1_1") (pintype "passive"))
    )
    (net (code "64") (name "Net-(P13-3)") (class "Default")
      (node (ref "P13") (pin "P$3") (pinfunction "3_P$3") (pintype "passive"))
      (node (ref "R14") (pin "1") (pinfunction "1_1") (pintype "passive"))
    )
    (net (code "65") (name "Net-(P14-3)") (class "Default")
      (node (ref "P14") (pin "P$3") (pinfunction "3_P$3") (pintype "passive"))
      (node (ref "R15") (pin "1") (pinfunction "1_1") (pintype "passive"))
    )
    (net (code "66") (name "Net-(P15-3)") (class "Default")
      (node (ref "P15") (pin "P$3") (pinfunction "3_P$3") (pintype "passive"))
      (node (ref "R16") (pin "1") (pinfunction "1_1") (pintype "passive"))
    )
    (net (code "67") (name "Net-(P16-3)") (class "Default")
      (node (ref "P16") (pin "P$3") (pinfunction "3_P$3") (pintype "passive"))
      (node (ref "R17") (pin "1") (pinfunction "1_1") (pintype "passive"))
    )
    (net (code "68") (name "Net-(P18-3)") (class "Default")
      (node (ref "P18") (pin "P$3") (pinfunction "3_P$3") (pintype "passive"))
      (node (ref "R19") (pin "1") (pinfunction "1_1") (pintype "passive"))
    )
    (net (code "69") (name "Net-(P19-3)") (class "Default")
      (node (ref "P19") (pin "P$3") (pinfunction "3_P$3") (pintype "passive"))
      (node (ref "R20") (pin "1") (pinfunction "1_1") (pintype "passive"))
    )
    (net (code "70") (name "Net-(P21-3)") (class "Default")
      (node (ref "P21") (pin "P$3") (pinfunction "3_P$3") (pintype "passive"))
      (node (ref "R18") (pin "1") (pinfunction "1_1") (pintype "passive"))
    )
    (net (code "71") (name "Net-(P22-3)") (class "Default")
      (node (ref "P22") (pin "P$3") (pinfunction "3_P$3") (pintype "passive"))
      (node (ref "R1") (pin "1") (pinfunction "1_1") (pintype "passive"))
    )
    (net (code "72") (name "Net-(Q1-D)") (class "Default")
      (node (ref "JP8") (pin "10") (pinfunction "10_10") (pintype "passive"))
      (node (ref "JP8") (pin "9") (pinfunction "9_9") (pintype "passive"))
      (node (ref "Q1") (pin "3") (pinfunction "D_3") (pintype "passive"))
    )
    (net (code "73") (name "Net-(Q2-D)") (class "Default")
      (node (ref "JP8") (pin "1") (pinfunction "1_1") (pintype "passive"))
      (node (ref "JP8") (pin "2") (pinfunction "2_2") (pintype "passive"))
      (node (ref "Q2") (pin "3") (pinfunction "D_3") (pintype "passive"))
    )
    (net (code "74") (name "unconnected-(IC2-VE-Pad7)") (class "Default")
      (node (ref "IC2") (pin "7") (pinfunction "VE_7") (pintype "passive"))
    )
    (net (code "75") (name "unconnected-(JP1-Pad5)") (class "Default")
      (node (ref "JP1") (pin "5") (pinfunction "5_5") (pintype "passive"))
    )
    (net (code "76") (name "unconnected-(JP2-Pad18)") (class "Default")
      (node (ref "JP2") (pin "18") (pinfunction "18_18") (pintype "passive"))
    )
    (net (code "77") (name "unconnected-(P1-4-PadP$2)") (class "Default")
      (node (ref "P1") (pin "P$2") (pinfunction "4_P$2") (pintype "passive"))
    )
    (net (code "78") (name "unconnected-(P2-4-PadP$2)") (class "Default")
      (node (ref "P2") (pin "P$2") (pinfunction "4_P$2") (pintype "passive"))
    )
    (net (code "79") (name "unconnected-(P3-4-PadP$2)") (class "Default")
      (node (ref "P3") (pin "P$2") (pinfunction "4_P$2") (pintype "passive"))
    )
    (net (code "80") (name "unconnected-(P4-4-PadP$2)") (class "Default")
      (node (ref "P4") (pin "P$2") (pinfunction "4_P$2") (pintype "passive"))
    )
    (net (code "81") (name "unconnected-(P5-4-PadP$2)") (class "Default")
      (node (ref "P5") (pin "P$2") (pinfunction "4_P$2") (pintype "passive"))
    )
    (net (code "82") (name "unconnected-(P6-4-PadP$2)") (class "Default")
      (node (ref "P6") (pin "P$2") (pinfunction "4_P$2") (pintype "passive"))
    )
    (net (code "83") (name "unconnected-(P7-4-PadP$2)") (class "Default")
      (node (ref "P7") (pin "P$2") (pinfunction "4_P$2") (pintype "passive"))
    )
    (net (code "84") (name "unconnected-(P8-4-PadP$2)") (class "Default")
      (node (ref "P8") (pin "P$2") (pinfunction "4_P$2") (pintype "passive"))
    )
    (net (code "85") (name "unconnected-(P9-4-PadP$2)") (class "Default")
      (node (ref "P9") (pin "P$2") (pinfunction "4_P$2") (pintype "passive"))
    )
    (net (code "86") (name "unconnected-(P10-4-PadP$2)") (class "Default")
      (node (ref "P10") (pin "P$2") (pinfunction "4_P$2") (pintype "passive"))
    )
    (net (code "87") (name "unconnected-(P11-4-PadP$2)") (class "Default")
      (node (ref "P11") (pin "P$2") (pinfunction "4_P$2") (pintype "passive"))
    )
    (net (code "88") (name "unconnected-(P12-4-PadP$2)") (class "Default")
      (node (ref "P12") (pin "P$2") (pinfunction "4_P$2") (pintype "passive"))
    )
    (net (code "89") (name "unconnected-(P13-4-PadP$2)") (class "Default")
      (node (ref "P13") (pin "P$2") (pinfunction "4_P$2") (pintype "passive"))
    )
    (net (code "90") (name "unconnected-(P14-4-PadP$2)") (class "Default")
      (node (ref "P14") (pin "P$2") (pinfunction "4_P$2") (pintype "passive"))
    )
    (net (code "91") (name "unconnected-(P15-4-PadP$2)") (class "Default")
      (node (ref "P15") (pin "P$2") (pinfunction "4_P$2") (pintype "passive"))
    )
    (net (code "92") (name "unconnected-(P16-4-PadP$2)") (class "Default")
      (node (ref "P16") (pin "P$2") (pinfunction "4_P$2") (pintype "passive"))
    )
    (net (code "93") (name "unconnected-(P18-4-PadP$2)") (class "Default")
      (node (ref "P18") (pin "P$2") (pinfunction "4_P$2") (pintype "passive"))
    )
    (net (code "94") (name "unconnected-(P19-4-PadP$2)") (class "Default")
      (node (ref "P19") (pin "P$2") (pinfunction "4_P$2") (pintype "passive"))
    )
    (net (code "95") (name "unconnected-(P21-4-PadP$2)") (class "Default")
      (node (ref "P21") (pin "P$2") (pinfunction "4_P$2") (pintype "passive"))
    )
    (net (code "96") (name "unconnected-(P22-4-PadP$2)") (class "Default")
      (node (ref "P22") (pin "P$2") (pinfunction "4_P$2") (pintype "passive"))
    )
  )
)
